# 08_-_Voltage_Regulator.net
KiCad netlist of a schematic drawn in Altium Designer
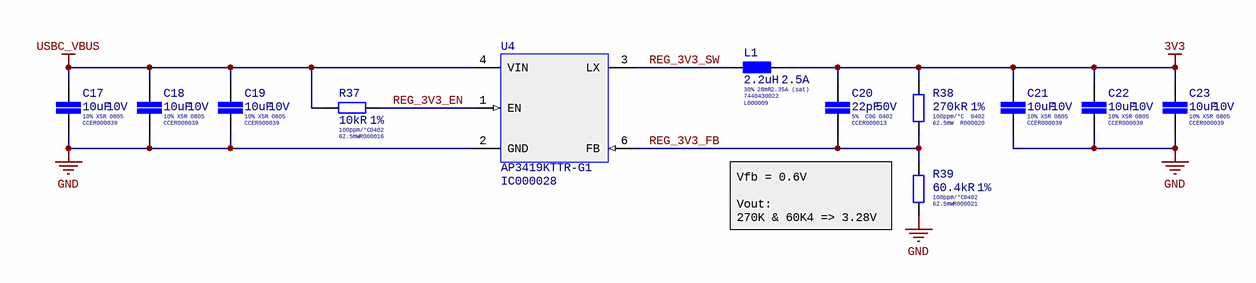
[diagram p0: [08] - Voltage Regulator.SchDoc]

(export (version "E")
  (design (tool "Eeschema 10.0.6"))
  (components
    (comp (ref "C17")
      (value "10uF 10V")
      (footprint "CAP-SMD-0805-1.35MM-IPC-MED")
      (description "CAP CER 10U 10V X5R 10% SMD 0805 85C SAMSUNG")
      (fields
        (field (name "VOLTAGE") "10V")
        (field (name "INTERNAL PART NUMBER") "CCER000039")
        (field (name "TOLERANCE") "10%")
        (field (name "VOLTAGE RATING") "10V")
        (field (name "DIELECTRIC") "X5R")
        (field (name "CASE/PACKAGE") "0805")
        (field (name "CAPACITANCE") "10uF")
      )
      (libsource (lib "Altium_Lib_Standard") (part "CL21A106KPFNNNG"))
    )
    (comp (ref "C18")
      (value "10uF 10V")
      (footprint "CAP-SMD-0805-1.35MM-IPC-MED")
      (description "CAP CER 10U 10V X5R 10% SMD 0805 85C SAMSUNG")
      (fields
        (field (name "VOLTAGE") "10V")
        (field (name "INTERNAL PART NUMBER") "CCER000039")
        (field (name "TOLERANCE") "10%")
        (field (name "VOLTAGE RATING") "10V")
        (field (name "DIELECTRIC") "X5R")
        (field (name "CASE/PACKAGE") "0805")
        (field (name "CAPACITANCE") "10uF")
      )
      (libsource (lib "Altium_Lib_Standard") (part "CL21A106KPFNNNG"))
    )
    (comp (ref "C19")
      (value "10uF 10V")
      (footprint "CAP-SMD-0805-1.35MM-IPC-MED")
      (description "CAP CER 10U 10V X5R 10% SMD 0805 85C SAMSUNG")
      (fields
        (field (name "VOLTAGE") "10V")
        (field (name "INTERNAL PART NUMBER") "CCER000039")
        (field (name "TOLERANCE") "10%")
        (field (name "VOLTAGE RATING") "10V")
        (field (name "DIELECTRIC") "X5R")
        (field (name "CASE/PACKAGE") "0805")
        (field (name "CAPACITANCE") "10uF")
      )
      (libsource (lib "Altium_Lib_Standard") (part "CL21A106KPFNNNG"))
    )
    (comp (ref "C20")
      (value "22pF 50V")
      (footprint "CAP-SMD-0402-0.55MM-IPC-MED")
      (description "CAP CER 22P 50V C0G 5% SMD 0402 125C SAMSUNG")
      (fields
        (field (name "MANUFACTURER") "Samsung")
        (field (name "MANUFACTURER PART NUMBER") "CL05C220JB5NNNC")
        (field (name "INTERNAL PART NUMBER") "CCER000013")
        (field (name "VOLTAGE RATING") "50V")
        (field (name "TOLERANCE") "5%")
        (field (name "DIELECTRIC") "C0G")
        (field (name "CASE/PACKAGE") "0402")
        (field (name "CAPACITANCE") "22pF")
      )
      (libsource (lib "Altium_Lib_Standard") (part "CL05C220JB5NNNC"))
    )
    (comp (ref "C21")
      (value "10uF 10V")
      (footprint "CAP-SMD-0805-1.35MM-IPC-MED")
      (description "CAP CER 10U 10V X5R 10% SMD 0805 85C SAMSUNG")
      (fields
        (field (name "VOLTAGE") "10V")
        (field (name "INTERNAL PART NUMBER") "CCER000039")
        (field (name "TOLERANCE") "10%")
        (field (name "VOLTAGE RATING") "10V")
        (field (name "DIELECTRIC") "X5R")
        (field (name "CASE/PACKAGE") "0805")
        (field (name "CAPACITANCE") "10uF")
      )
      (libsource (lib "Altium_Lib_Standard") (part "CL21A106KPFNNNG"))
    )
    (comp (ref "C22")
      (value "10uF 10V")
      (footprint "CAP-SMD-0805-1.35MM-IPC-MED")
      (description "CAP CER 10U 10V X5R 10% SMD 0805 85C SAMSUNG")
      (fields
        (field (name "VOLTAGE") "10V")
        (field (name "INTERNAL PART NUMBER") "CCER000039")
        (field (name "TOLERANCE") "10%")
        (field (name "VOLTAGE RATING") "10V")
        (field (name "DIELECTRIC") "X5R")
        (field (name "CASE/PACKAGE") "0805")
        (field (name "CAPACITANCE") "10uF")
      )
      (libsource (lib "Altium_Lib_Standard") (part "CL21A106KPFNNNG"))
    )
    (comp (ref "C23")
      (value "10uF 10V")
      (footprint "CAP-SMD-0805-1.35MM-IPC-MED")
      (description "CAP CER 10U 10V X5R 10% SMD 0805 85C SAMSUNG")
      (fields
        (field (name "VOLTAGE") "10V")
        (field (name "INTERNAL PART NUMBER") "CCER000039")
        (field (name "TOLERANCE") "10%")
        (field (name "VOLTAGE RATING") "10V")
        (field (name "DIELECTRIC") "X5R")
        (field (name "CASE/PACKAGE") "0805")
        (field (name "CAPACITANCE") "10uF")
      )
      (libsource (lib "Altium_Lib_Standard") (part "CL21A106KPFNNNG"))
    )
    (comp (ref "L1")
      (value "7440430022")
      (footprint "IND-SMD-7440430022-3MM")
      (description "IND 2U2 2A5 28mR 30% SMD FERRITE WURTH")
      (fields
        (field (name "MANUFACTURER") "Wurth Electronics")
        (field (name "TOLERANCE") "30%")
        (field (name "SATURATION CURRENT") "2.35A (sat)")
        (field (name "INTERNAL PART NUMBER") "L000009")
        (field (name "MANUFACTURER PART NUMBER") "7440430022")
        (field (name "INDUCTANCE TOLERANCE") "30%")
        (field (name "DC RESISTANCE (DCR)") "28mR")
        (field (name "CURRENT RATING") "2.5A")
        (field (name "INDUCTANCE") "2.2uH")
      )
      (libsource (lib "Altium_Lib_Standard") (part "7440430022"))
    )
    (comp (ref "R37")
      (value "10kR 1%")
      (footprint "RES-SMD-0402-0.4MM-IPC-MED")
      (description "RES 10K 1% 1/16W SMD 0402 YAEGO")
      (fields
        (field (name "MANUFACTURER") "Yageo")
        (field (name "MANUFACTURER PART NUMBER") "RC0402FR-0710KL")
        (field (name "TOLERANCE") "1%")
        (field (name "TEMPERATURE COEFFICIENT") "100ppm/°C")
        (field (name "RESISTANCE") "10kR")
        (field (name "POWER RATING") "62.5mW")
        (field (name "CASE CODE (IMPERIAL)") "0402")
        (field (name "INTERNAL PART NUMBER") "R000016")
      )
      (libsource (lib "Altium_Lib_Standard") (part "RC0402FR-0710KL"))
    )
    (comp (ref "R38")
      (value "RC0402FR-07270KL")
      (footprint "RES-SMD-0402-0.4MM-IPC-MED")
      (description "RES 270K 1% 1/16W SMD 0402 YAEGO")
      (fields
        (field (name "MANUFACTURER") "Yageo")
        (field (name "CASE/PACKAGE") "0402")
        (field (name "TOLERANCE") "1%")
        (field (name "TEMPERATURE COEFFICIENT") "100ppm/°C")
        (field (name "RESISTANCE") "270kR")
        (field (name "MAX POWER DISSIPATION") "62.5mW")
        (field (name "INTERNAL PART NUMBER") "R000020")
      )
      (libsource (lib "Altium_Lib_Standard") (part "RC0402FR-07270KL"))
    )
    (comp (ref "R39")
      (value "RC0402FR-0760K4L")
      (footprint "RES-SMD-0402-0.4MM-IPC-MED")
      (description "RES 60K4 1% 1/16W SMD 0402 YAEGO")
      (fields
        (field (name "MANUFACTURER") "Yageo")
        (field (name "RESISTANCE") "60.4kR")
        (field (name "TOLERANCE") "1%")
        (field (name "TEMPERATURE COEFFICIENT") "100ppm/°C")
        (field (name "CASE/PACKAGE") "0402")
        (field (name "POWER RATING") "62.5mW")
        (field (name "INTERNAL PART NUMBER") "R000021")
      )
      (libsource (lib "Altium_Lib_Standard") (part "RC0402FR-0760K4L"))
    )
    (comp (ref "U4")
      (value "AP3419KTTR-G1")
      (footprint "SOT-23-6-H1MM-DIODES-INC")
      (description "IC REGULATOR BUCK 2A SYNC 1MHZ SOT-23-6")
      (fields (field (name "MANUFACTURER") "Diodes") (field (name "INTERNAL PART NUMBER") "IC000028"))
      (libsource (lib "Altium_Lib_Standard") (part "AP3419KTTR-G1"))
    )
  )
  (nets
    (net (code "1") (name "/REG_3V3_EN") (class "Default")
      (node (ref "R37") (pin "2") (pinfunction "2_2") (pintype "passive"))
      (node (ref "U4") (pin "1") (pinfunction "EN_1") (pintype "input"))
    )
    (net (code "2") (name "/REG_3V3_FB") (class "Default")
      (node (ref "C20") (pin "2") (pinfunction "2_2") (pintype "passive"))
      (node (ref "R38") (pin "2") (pinfunction "2_2") (pintype "passive"))
      (node (ref "R39") (pin "1") (pinfunction "1_1") (pintype "passive"))
      (node (ref "U4") (pin "6") (pinfunction "FB_6") (pintype "input"))
    )
    (net (code "3") (name "/REG_3V3_SW") (class "Default")
      (node (ref "L1") (pin "1") (pinfunction "1_1") (pintype "passive"))
      (node (ref "U4") (pin "3") (pinfunction "LX_3") (pintype "power_in"))
    )
    (net (code "4") (name "3V3") (class "Default")
      (node (ref "C20") (pin "1") (pinfunction "1_1") (pintype "passive"))
      (node (ref "C21") (pin "1") (pinfunction "1_1") (pintype "passive"))
      (node (ref "C22") (pin "1") (pinfunction "1_1") (pintype "passive"))
      (node (ref "C23") (pin "1") (pinfunction "1_1") (pintype "passive"))
      (node (ref "L1") (pin "2") (pinfunction "2_2") (pintype "passive"))
      (node (ref "R38") (pin "1") (pinfunction "1_1") (pintype "passive"))
    )
    (net (code "5") (name "GND") (class "Default")
      (node (ref "C17") (pin "2") (pinfunction "2_2") (pintype "passive"))
      (node (ref "C18") (pin "2") (pinfunction "2_2") (pintype "passive"))
      (node (ref "C19") (pin "2") (pinfunction "2_2") (pintype "passive"))
      (node (ref "C21") (pin "2") (pinfunction "2_2") (pintype "passive"))
      (node (ref "C22") (pin "2") (pinfunction "2_2") (pintype "passive"))
      (node (ref "C23") (pin "2") (pinfunction "2_2") (pintype "passive"))
      (node (ref "R39") (pin "2") (pinfunction "2_2") (pintype "passive"))
      (node (ref "U4") (pin "2") (pinfunction "GND_2") (pintype "power_in"))
    )
    (net (code "6") (name "USBC_VBUS") (class "Default")
      (node (ref "C17") (pin "1") (pinfunction "1_1") (pintype "passive"))
      (node (ref "C18") (pin "1") (pinfunction "1_1") (pintype "passive"))
      (node (ref "C19") (pin "1") (pinfunction "1_1") (pintype "passive"))
      (node (ref "R37") (pin "1") (pinfunction "1_1") (pintype "passive"))
      (node (ref "U4") (pin "4") (pinfunction "VIN_4") (pintype "power_in"))
    )
  )
)
